# MIL_STD_1275D.net
KiCad netlist of a schematic drawn in Altium Designer
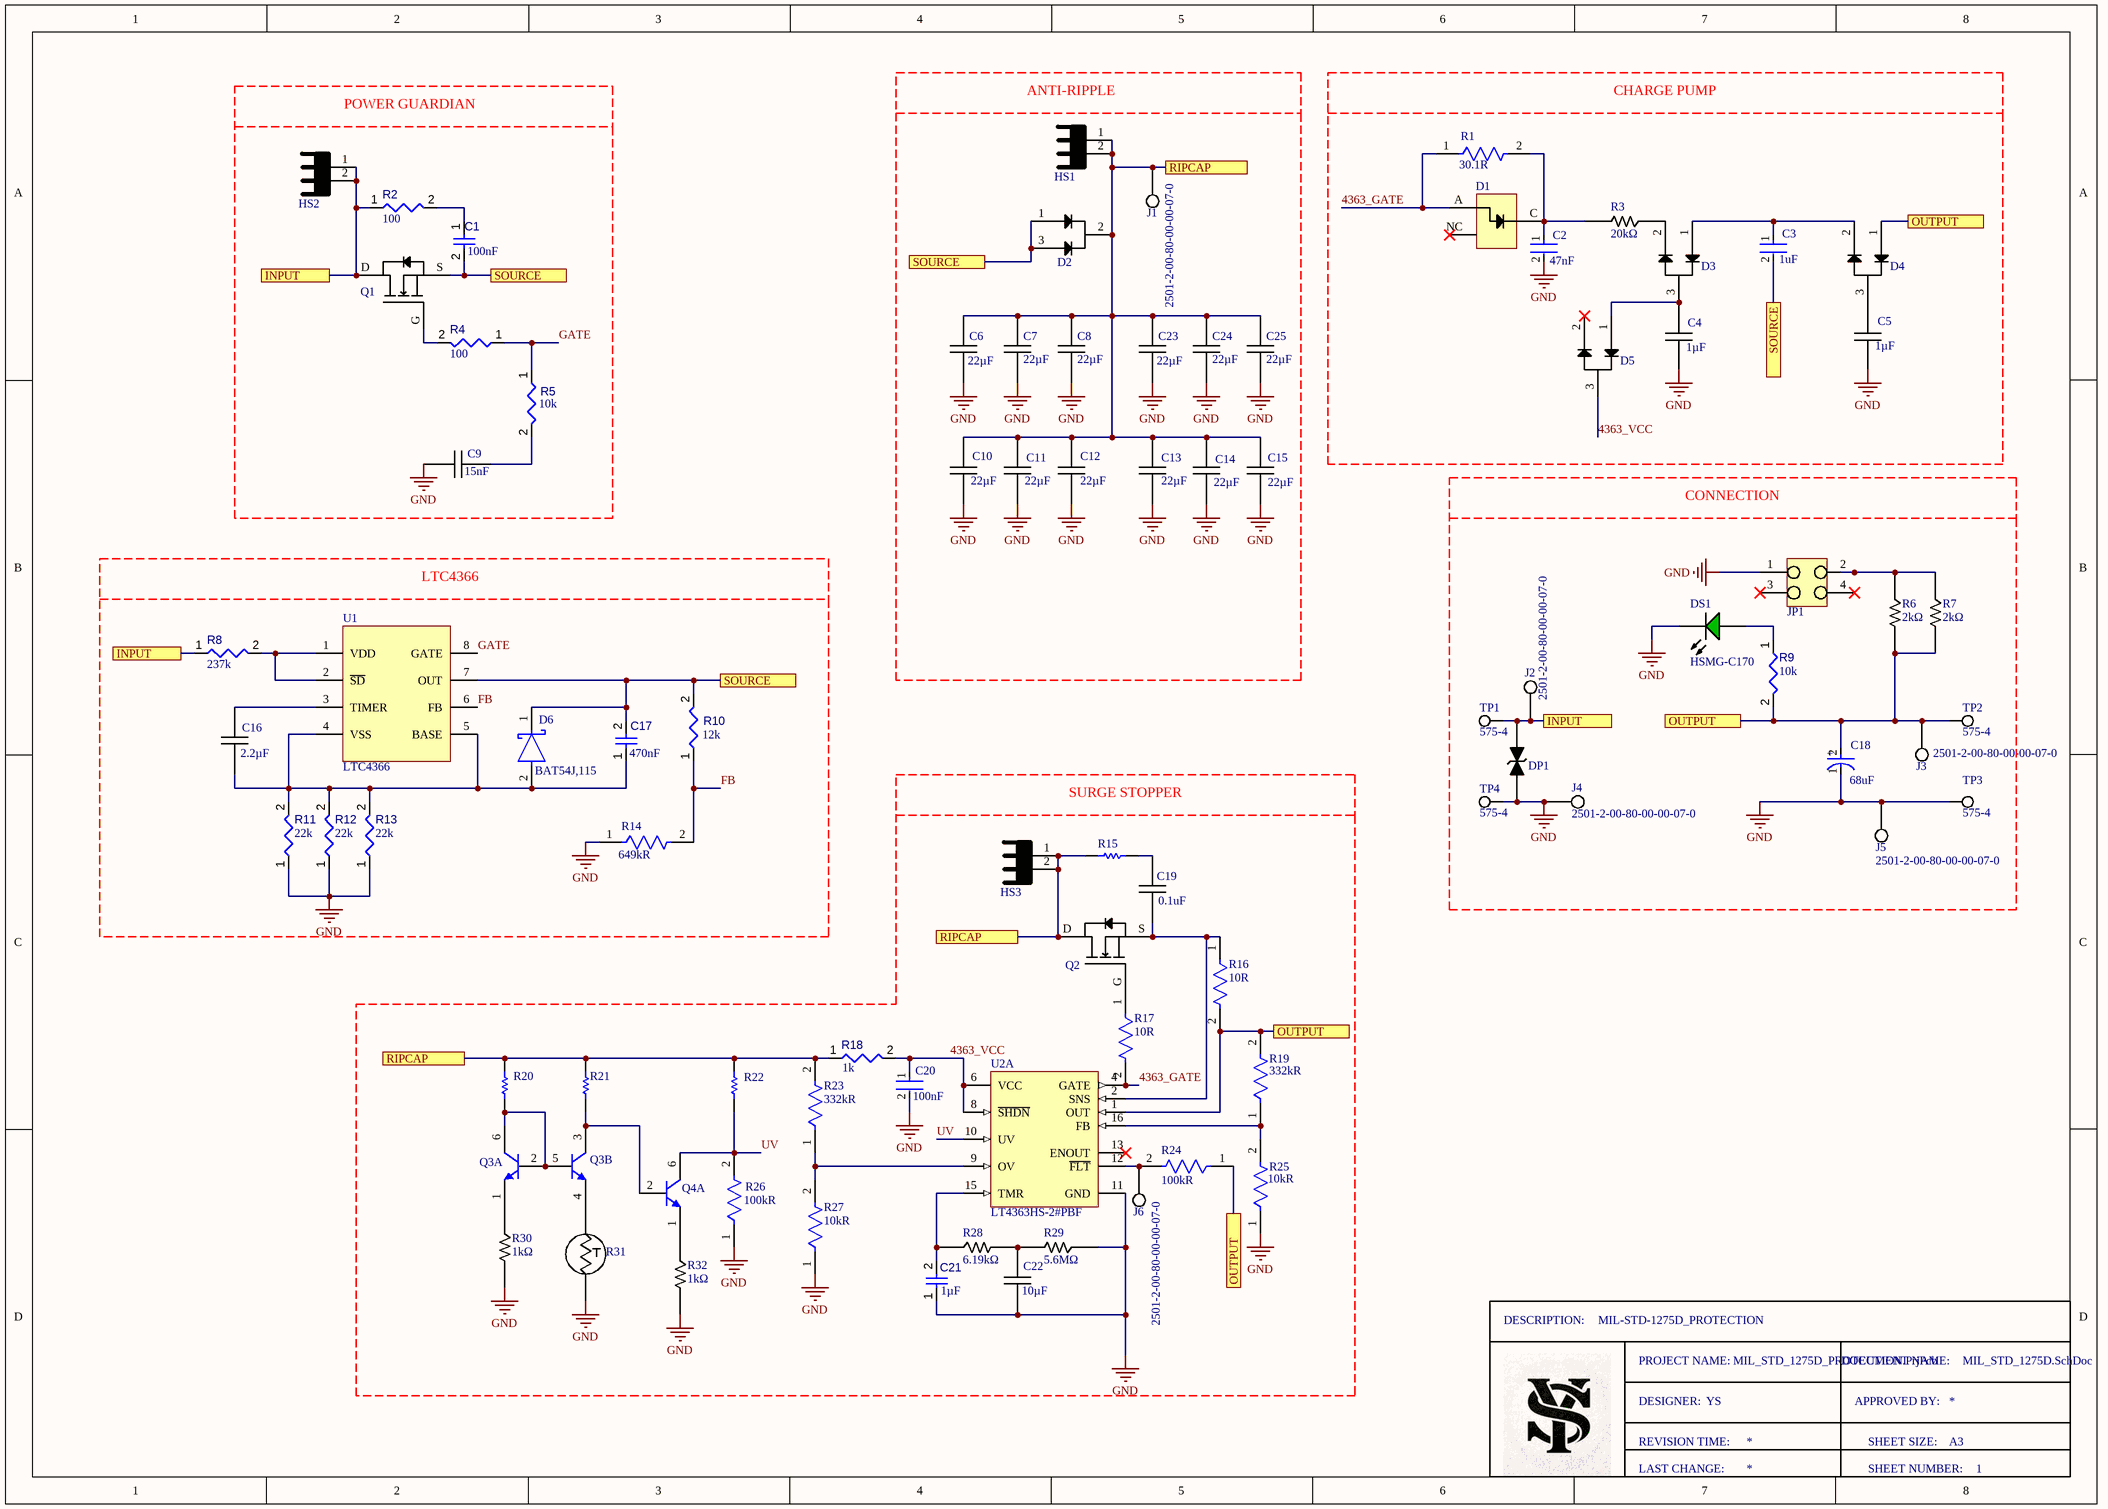
[diagram p0: MIL_STD_1275D.SchDoc]

(export (version "E")
  (design (tool "Eeschema 10.0.6"))
  (components
    (comp (ref "C1")
      (value "100nF")
      (footprint "CAPC0402(1005)60_L")
      (description "Chip Capacitor, 100nF +/-20%, 25V, 0402, Thickness 0.6 mm")
      (fields (field (name "TOLERANCE") "10%") (field (name "Comment") "Capacitor 100nF +/-20% 25V 0402"))
      (libsource (lib "Yigithan Sarı") (part "CAP-NP-2"))
    )
    (comp (ref "C2")
      (value "C2012X7R2A473K125AA")
      (footprint "FP-C2012-125-0_2-IPC_B")
      (description "Multilayer Ceramic Capacitors 47nF ±10% 100V X7R SMD 0805")
      (fields
        (field (name "VOLTAGE") "100V")
        (field (name "CAPACITANCE") "47nF")
        (field (name "TOLERANCE") "10%")
      )
      (libsource (lib "Altium Content Vault") (part "b4654b650e69147ec39a6b967a45e02"))
    )
    (comp (ref "C3")
      (value "C5750X7R2E105K230KA")
      (footprint "FP-C5750-230-0_4-MFG")
      (description "Multilayer Ceramic Capacitors 1uF ±10% 250V X7R SMD 2220")
      (fields
        (field (name "TOLERANCE") "10%")
        (field (name "VOLTAGE") "250V")
        (field (name "CAPACITANCE") "1uF")
      )
      (libsource (lib "Altium Content Vault") (part "02cd4be3c70576c341d710602a673aa"))
    )
    (comp (ref "C4")
      (value "1µF")
      (footprint "CAP_2220")
      (description "250V 1uF X7R 卤10% 2220 Multilayer Ceramic Capacitors MLCC - SMD/SMT ROHS")
      (fields
        (field (name "MANUFACTURER") "TDK")
        (field (name "MANUFACTURER PART NUMBER") "C5750X7R2E105K230KA")
        (field (name "DESIGNED BY") "YS")
      )
      (libsource (lib "DC2150A") (part "C5750X7R2E105K230KA"))
    )
    (comp (ref "C5")
      (value "1µF")
      (footprint "CAP_2220")
      (description "250V 1uF X7R 卤10% 2220 Multilayer Ceramic Capacitors MLCC - SMD/SMT ROHS")
      (fields
        (field (name "MANUFACTURER") "TDK")
        (field (name "MANUFACTURER PART NUMBER") "C5750X7R2E105K230KA")
        (field (name "DESIGNED BY") "YS")
      )
      (libsource (lib "DC2150A") (part "C5750X7R2E105K230KA"))
    )
    (comp (ref "C6")
      (value "22µF")
      (footprint "2 J-LEAD CAP")
      (description "Multilayer Ceramic Capacitor, CKG Series, 22 - F, - 20%, X7S, 100 V, 2220 [5750 Metric]")
      (fields
        (field (name "MANUFACTURER") "TDK")
        (field (name "MANUFACTURER PART NUMBER") "CKG57NX7S2A226M500JH")
        (field (name "DESIGNED BY") "YS")
      )
      (libsource (lib "DC2150A") (part "CKG57NX7S2A226M500JH"))
    )
    (comp (ref "C7")
      (value "22µF")
      (footprint "2 J-LEAD CAP")
      (description "Multilayer Ceramic Capacitor, CKG Series, 22 - F, - 20%, X7S, 100 V, 2220 [5750 Metric]")
      (fields
        (field (name "MANUFACTURER") "TDK")
        (field (name "MANUFACTURER PART NUMBER") "CKG57NX7S2A226M500JH")
        (field (name "DESIGNED BY") "YS")
      )
      (libsource (lib "DC2150A") (part "CKG57NX7S2A226M500JH"))
    )
    (comp (ref "C8")
      (value "22µF")
      (footprint "2 J-LEAD CAP")
      (description "Multilayer Ceramic Capacitor, CKG Series, 22 - F, - 20%, X7S, 100 V, 2220 [5750 Metric]")
      (fields
        (field (name "MANUFACTURER") "TDK")
        (field (name "MANUFACTURER PART NUMBER") "CKG57NX7S2A226M500JH")
        (field (name "DESIGNED BY") "YS")
      )
      (libsource (lib "DC2150A") (part "CKG57NX7S2A226M500JH"))
    )
    (comp (ref "C9")
      (value "15nF")
      (footprint "CAP_1206")
      (description "Cap Ceramic 0.015uF 100V X7R 10% Pad SMD 1206 125C T/R")
      (fields
        (field (name "MANUFACTURER") "Yageo Group")
        (field (name "MANUFACTURER PART NUMBER") "C1206C153K1RACTU")
        (field (name "DESIGNED BY") "YS")
      )
      (libsource (lib "DC2150A") (part "C1206C153K1RACTU (2)"))
    )
    (comp (ref "C10")
      (value "22µF")
      (footprint "2 J-LEAD CAP")
      (description "Multilayer Ceramic Capacitor, CKG Series, 22 - F, - 20%, X7S, 100 V, 2220 [5750 Metric]")
      (fields
        (field (name "MANUFACTURER") "TDK")
        (field (name "MANUFACTURER PART NUMBER") "CKG57NX7S2A226M500JH")
        (field (name "DESIGNED BY") "YS")
      )
      (libsource (lib "DC2150A") (part "CKG57NX7S2A226M500JH"))
    )
    (comp (ref "C11")
      (value "22µF")
      (footprint "2 J-LEAD CAP")
      (description "Multilayer Ceramic Capacitor, CKG Series, 22 - F, - 20%, X7S, 100 V, 2220 [5750 Metric]")
      (fields
        (field (name "MANUFACTURER") "TDK")
        (field (name "MANUFACTURER PART NUMBER") "CKG57NX7S2A226M500JH")
        (field (name "DESIGNED BY") "YS")
      )
      (libsource (lib "DC2150A") (part "CKG57NX7S2A226M500JH"))
    )
    (comp (ref "C12")
      (value "22µF")
      (footprint "2 J-LEAD CAP")
      (description "Multilayer Ceramic Capacitor, CKG Series, 22 - F, - 20%, X7S, 100 V, 2220 [5750 Metric]")
      (fields
        (field (name "MANUFACTURER") "TDK")
        (field (name "MANUFACTURER PART NUMBER") "CKG57NX7S2A226M500JH")
        (field (name "DESIGNED BY") "YS")
      )
      (libsource (lib "DC2150A") (part "CKG57NX7S2A226M500JH"))
    )
    (comp (ref "C13")
      (value "22µF")
      (footprint "2 J-LEAD CAP")
      (description "Multilayer Ceramic Capacitor, CKG Series, 22 - F, - 20%, X7S, 100 V, 2220 [5750 Metric]")
      (fields
        (field (name "MANUFACTURER") "TDK")
        (field (name "MANUFACTURER PART NUMBER") "CKG57NX7S2A226M500JH")
        (field (name "DESIGNED BY") "YS")
      )
      (libsource (lib "DC2150A") (part "CKG57NX7S2A226M500JH"))
    )
    (comp (ref "C14")
      (value "22µF")
      (footprint "2 J-LEAD CAP")
      (description "Multilayer Ceramic Capacitor, CKG Series, 22 - F, - 20%, X7S, 100 V, 2220 [5750 Metric]")
      (fields
        (field (name "MANUFACTURER") "TDK")
        (field (name "MANUFACTURER PART NUMBER") "CKG57NX7S2A226M500JH")
        (field (name "DESIGNED BY") "YS")
      )
      (libsource (lib "DC2150A") (part "CKG57NX7S2A226M500JH"))
    )
    (comp (ref "C15")
      (value "22µF")
      (footprint "2 J-LEAD CAP")
      (description "Multilayer Ceramic Capacitor, CKG Series, 22 - F, - 20%, X7S, 100 V, 2220 [5750 Metric]")
      (fields
        (field (name "MANUFACTURER") "TDK")
        (field (name "MANUFACTURER PART NUMBER") "CKG57NX7S2A226M500JH")
        (field (name "DESIGNED BY") "YS")
      )
      (libsource (lib "DC2150A") (part "CKG57NX7S2A226M500JH"))
    )
    (comp (ref "C16")
      (value "2.2µF")
      (footprint "CAP_0805")
      (description "25V 2.2uF X7R ±10% 0805 Multilayer Ceramic Capacitors MLCC - SMD/SMT ROHS")
      (fields
        (field (name "MANUFACTURER") "TDK")
        (field (name "MANUFACTURER PART NUMBER") "CGA4J3X7R1E225K125AB")
        (field (name "DESIGNED BY") "YS")
      )
      (libsource (lib "DC2150A") (part "CGA4J3X7R1E225K125AB"))
    )
    (comp (ref "C17")
      (value "470nF")
      (footprint "CAPC0603(1608)100_L")
      (description "Chip Capacitor, 470nF +/-20%, 25V, 0603, Thickness 1 mm")
      (fields (field (name "TOLERANCE") "10%") (field (name "Comment") "Capacitor 470nF +/-20% 25V 0603"))
      (libsource (lib "Yigithan Sarı") (part "CAP-NP-2"))
    )
    (comp (ref "C18")
      (value "50SVPF68M")
      (footprint "FP-OS-CON-SMT-F12-MFG")
      (description "Conductive Polymer Aluminum Solid Capacitors (OS-CON) 68uF ±20% 50V RADIAL SMT 10x12.6mm")
      (fields
        (field (name "CAPACITANCE") "68uF")
        (field (name "TOLERANCE") "20%")
        (field (name "VOLTAGE") "50V")
      )
      (libsource (lib "Altium Content Vault") (part "a7907c86e72a156c28511143de7831b"))
    )
    (comp (ref "C19")
      (value "0.1uF")
      (footprint "CAP_1210")
      (description "SMD Comm X7R 1210 (3225Metric) ceramic capacitor 0.126Lx0.098W 3.20mmx2.50mm X7R ±10% 0.1muF")
      (fields (field (name "Comment") "CAP_CER_1210_0.1uF"))
      (libsource (lib "DC2150A") (part "C1210C104K1RAC7025 Yageo Group"))
    )
    (comp (ref "C20")
      (value "C2012X7R2A104K125AA")
      (footprint "FP-C2012-125-0_2-IPC_B")
      (description "Multilayer Ceramic Capacitors 100nF ±10% 100V X7R SMD 0805")
      (fields
        (field (name "VOLTAGE") "100V")
        (field (name "CAPACITANCE") "100nF")
        (field (name "TOLERANCE") "10%")
      )
      (libsource (lib "Altium Content Vault") (part "b4654b650e69147ec39a6b967a45e02"))
    )
    (comp (ref "C21")
      (value "1µF")
      (footprint "CAPC1608X90X35ML15T15")
      (description "Chip Capacitor, 1 uF, +/- 10%, 16 V, 0603 (1608 Metric)")
      (fields (field (name "TOLERANCE") "10%") (field (name "Comment") "Capacitor 1uF +/- 10% 16V 0603"))
      (libsource (lib "Yigithan Sarı") (part "CAP-NP-2"))
    )
    (comp (ref "C22")
      (value "10µF")
      (footprint "CAP_0805")
      (description "16V 10uF X7R 卤10% 0805 Multilayer Ceramic Capacitors MLCC - SMD/SMT ROHS")
      (fields
        (field (name "MANUFACTURER") "Samsung Electro-Mechanics")
        (field (name "MANUFACTURER PART NUMBER") "CL21B106KOQNNNE")
        (field (name "DESIGNED BY") "YS")
      )
      (libsource (lib "DC2150A") (part "CL21B106KOQNNNE"))
    )
    (comp (ref "C23")
      (value "22µF")
      (footprint "2 J-LEAD CAP")
      (description "Multilayer Ceramic Capacitor, CKG Series, 22 - F, - 20%, X7S, 100 V, 2220 [5750 Metric]")
      (fields
        (field (name "MANUFACTURER") "TDK")
        (field (name "MANUFACTURER PART NUMBER") "CKG57NX7S2A226M500JH")
        (field (name "DESIGNED BY") "YS")
      )
      (libsource (lib "DC2150A") (part "CKG57NX7S2A226M500JH"))
    )
    (comp (ref "C24")
      (value "22µF")
      (footprint "2 J-LEAD CAP")
      (description "Multilayer Ceramic Capacitor, CKG Series, 22 - F, - 20%, X7S, 100 V, 2220 [5750 Metric]")
      (fields
        (field (name "MANUFACTURER") "TDK")
        (field (name "MANUFACTURER PART NUMBER") "CKG57NX7S2A226M500JH")
        (field (name "DESIGNED BY") "YS")
      )
      (libsource (lib "DC2150A") (part "CKG57NX7S2A226M500JH"))
    )
    (comp (ref "C25")
      (value "22µF")
      (footprint "2 J-LEAD CAP")
      (description "Multilayer Ceramic Capacitor, CKG Series, 22 - F, - 20%, X7S, 100 V, 2220 [5750 Metric]")
      (fields
        (field (name "MANUFACTURER") "TDK")
        (field (name "MANUFACTURER PART NUMBER") "CKG57NX7S2A226M500JH")
        (field (name "DESIGNED BY") "YS")
      )
      (libsource (lib "DC2150A") (part "CKG57NX7S2A226M500JH"))
    )
    (comp (ref "D1")
      (value "DIODE_SMD_250V")
      (footprint "SOT_323")
      (description "Rectifier Diode, 1 Phase, 1 Element, 0.2A, 250V V(RRM), Silicon")
      (fields
        (field (name "MANUFACTURER") "Diodes Inc.")
        (field (name "MANUFACTURER PART NUMBER") "BAS21W-7-F")
      )
      (libsource (lib "DC2150A") (part "BAS21W-7-F"))
    )
    (comp (ref "D2")
      (value "Rectifier Diode, 1 Phase, 2 Element")
      (footprint "TO-247AD")
      (description "Rectifier Diode, 1 Phase, 2 Element, 15A, 400V V(RRM), Silicon, TO-247AD")
      (fields
        (field (name "MANUFACTURER") "Vishay")
        (field (name "MANUFACTURER PART NUMBER") "FEP30GP-E3/45")
        (field (name "DESIGNED BY") "YS")
      )
      (libsource (lib "DC2150A") (part "FEP30GP-E3/45"))
    )
    (comp (ref "D3")
      (value "Rectifier Diode Small Signal Switching")
      (footprint "SOT-23")
      (description "Rectifier Diode Small Signal Switching 350V 0.225A 50ns 3-Pin SOT-23 T/R")
      (fields
        (field (name "MANUFACTURER") "Diodes Inc.")
        (field (name "MANUFACTURER PART NUMBER") "MMBD3004S-7-F")
        (field (name "DESIGNED BY") "YS")
      )
      (libsource (lib "DC2150A") (part "MMBD3004S-7-F"))
    )
    (comp (ref "D4")
      (value "Rectifier Diode Small Signal Switching")
      (footprint "SOT-23")
      (description "Rectifier Diode Small Signal Switching 350V 0.225A 50ns 3-Pin SOT-23 T/R")
      (fields
        (field (name "MANUFACTURER") "Diodes Inc.")
        (field (name "MANUFACTURER PART NUMBER") "MMBD3004S-7-F")
        (field (name "DESIGNED BY") "YS")
      )
      (libsource (lib "DC2150A") (part "MMBD3004S-7-F"))
    )
    (comp (ref "D5")
      (value "Rectifier Diode Small Signal Switching")
      (footprint "SOT-23")
      (description "Rectifier Diode Small Signal Switching 350V 0.225A 50ns 3-Pin SOT-23 T/R")
      (fields
        (field (name "MANUFACTURER") "Diodes Inc.")
        (field (name "MANUFACTURER PART NUMBER") "MMBD3004S-7-F")
        (field (name "DESIGNED BY") "YS")
      )
      (libsource (lib "DC2150A") (part "MMBD3004S-7-F"))
    )
    (comp (ref "D6")
      (value "BAT54J,115")
      (footprint "FP-SOD323F-MFG")
      (description "DIODE SCHOTTKY 30V 200MA SOD323F")
      (libsource (lib "Altium Content Vault") (part "1d6ec82d83fb6aee721767c19dac4b9"))
    )
    (comp (ref "DP1")
      (value "TVS")
      (footprint "DO-214AA")
      (description "Trans Voltage Suppressor Diode, 600W, 128V V(RWM), Bidirectional, 1 Element, Silicon, DO-214AA")
      (fields
        (field (name "MANUFACTURER") "Vishay")
        (field (name "MANUFACTURER PART NUMBER") "P6SMB150CA-E3/52")
      )
      (libsource (lib "DC2150A") (part "P6SMB150CA-E3/52"))
    )
    (comp (ref "DS1")
      (value "HSMG-C170")
      (footprint "AVAG-HSMX-C170_V")
      (description "Chip LED, Green, 2.2 V, -40 to 85 degC, 2-Pin SMD, Pb-Free, Tape and Reel")
      (fields (field (name "MANUFACTURER") "Avago"))
      (libsource (lib "Altium Content Vault") (part "LED_GREEN_A1K2-2"))
    )
    (comp (ref "HS1")
      (value "HEAT_SINK")
      (footprint "HS_VERTICAL")
      (description "Heat Sink SOT-32, TO-220, TOP-3 Aluminum Board Level, Vertical")
      (fields
        (field (name "MANUFACTURER") "ASSMANN WSW Components")
        (field (name "MANUFACTURER PART NUMBER") "V8813X")
        (field (name "DESIGNED BY") "YS")
      )
      (libsource (lib "DC2150A") (part "V8813X"))
    )
    (comp (ref "HS2")
      (value "HEAT_SINK")
      (footprint "HS_VERTICAL")
      (description "Heat Sink SOT-32, TO-220, TOP-3 Aluminum Board Level, Vertical")
      (fields
        (field (name "MANUFACTURER") "ASSMANN WSW Components")
        (field (name "MANUFACTURER PART NUMBER") "V8813X")
        (field (name "DESIGNED BY") "YS")
      )
      (libsource (lib "DC2150A") (part "V8813X"))
    )
    (comp (ref "HS3")
      (value "HEAT_SINK")
      (footprint "HS_VERTICAL")
      (description "Heat Sink SOT-32, TO-220, TOP-3 Aluminum Board Level, Vertical")
      (fields
        (field (name "MANUFACTURER") "ASSMANN WSW Components")
        (field (name "MANUFACTURER PART NUMBER") "V8813X")
        (field (name "DESIGNED BY") "YS")
      )
      (libsource (lib "DC2150A") (part "V8813X"))
    )
    (comp (ref "J1")
      (value "2501-2-00-80-00-00-07-0")
      (footprint "MILMAX_2501-2-00-80-00-00-07-0")
      (description "Terminal Turret Connector Single End 0.219 (5.56mm) Tin")
      (fields (field (name "MF") "Mill-Max Manufacturing"))
      (libsource (lib "2501-2-00-80-00-00-07-0") (part "2501-2-00-80-00-00-07-0"))
    )
    (comp (ref "J2")
      (value "2501-2-00-80-00-00-07-0")
      (footprint "MILMAX_2501-2-00-80-00-00-07-0")
      (description "Terminal Turret Connector Single End 0.219 (5.56mm) Tin")
      (fields (field (name "MF") "Mill-Max Manufacturing"))
      (libsource (lib "2501-2-00-80-00-00-07-0") (part "2501-2-00-80-00-00-07-0"))
    )
    (comp (ref "J3")
      (value "2501-2-00-80-00-00-07-0")
      (footprint "MILMAX_2501-2-00-80-00-00-07-0")
      (description "Terminal Turret Connector Single End 0.219 (5.56mm) Tin")
      (fields (field (name "MF") "Mill-Max Manufacturing"))
      (libsource (lib "2501-2-00-80-00-00-07-0") (part "2501-2-00-80-00-00-07-0"))
    )
    (comp (ref "J4")
      (value "2501-2-00-80-00-00-07-0")
      (footprint "MILMAX_2501-2-00-80-00-00-07-0")
      (description "Terminal Turret Connector Single End 0.219 (5.56mm) Tin")
      (fields (field (name "MF") "Mill-Max Manufacturing"))
      (libsource (lib "2501-2-00-80-00-00-07-0") (part "2501-2-00-80-00-00-07-0"))
    )
    (comp (ref "J5")
      (value "2501-2-00-80-00-00-07-0")
      (footprint "MILMAX_2501-2-00-80-00-00-07-0")
      (description "Terminal Turret Connector Single End 0.219 (5.56mm) Tin")
      (fields (field (name "MF") "Mill-Max Manufacturing"))
      (libsource (lib "2501-2-00-80-00-00-07-0") (part "2501-2-00-80-00-00-07-0"))
    )
    (comp (ref "J6")
      (value "2501-2-00-80-00-00-07-0")
      (footprint "MILMAX_2501-2-00-80-00-00-07-0")
      (description "Terminal Turret Connector Single End 0.219 (5.56mm) Tin")
      (fields (field (name "MF") "Mill-Max Manufacturing"))
      (libsource (lib "2501-2-00-80-00-00-07-0") (part "2501-2-00-80-00-00-07-0"))
    )
    (comp (ref "JP1")
      (value "CONNECTOR")
      (footprint "CONNECTOR_NRPN022PAEN-RC")
      (description "Board Connector, 4 Contact(s), 2 Row(s), Male, Straight, 0.079 inch Pitch, Solder Terminal")
      (fields
        (field (name "MANUFACTURER") "Sullins")
        (field (name "MANUFACTURER PART NUMBER") "NRPN022PAEN-RC")
      )
      (libsource (lib "DC2150A") (part "NRPN022PAEN-RC"))
    )
    (comp (ref "Q1")
      (value "N-CH MOSFET")
      (footprint "TO-3P")
      (description "PolarHT Series 300 V 88 A 40 mOhm Single N-Channel MOSFET - TO-3P")
      (fields
        (field (name "MANUFACTURER") "Littelfuse")
        (field (name "MANUFACTURER PART NUMBER") "IXTQ88N30P")
        (field (name "DESIGNED BY") "YS")
      )
      (libsource (lib "DC2150A") (part "IXTQ88N30P"))
    )
    (comp (ref "Q2")
      (value "N-CH MOSFET")
      (footprint "TO-3P")
      (description "Trans MOSFET N-CH 100V 170A 3-Pin(3+Tab) TO-3P")
      (fields
        (field (name "MANUFACTURER") "Littelfuse")
        (field (name "MANUFACTURER PART NUMBER") "IXTQ170N10P")
        (field (name "DESIGNED BY") "YS")
      )
      (libsource (lib "DC2150A") (part "IXTQ170N10P"))
    )
    (comp (ref "Q3")
      (value "MMDT5551-7-F")
      (footprint "DIOD-SOT-363-6_L")
      (fields (field (name "MANUFACTURER") "DiodesIncorporated"))
      (libsource (lib "Altium Content Vault") (part "BJT-NPN-EBC-EBC-6_A"))
    )
    (comp (ref "Q4")
      (value "MMDT5551-7-F")
      (footprint "DIOD-SOT-363-6_L")
      (fields (field (name "MANUFACTURER") "DiodesIncorporated"))
      (libsource (lib "Altium Content Vault") (part "BJT-NPN-EBC-EBC-6_A"))
    )
    (comp (ref "R1")
      (value "CRCW080530R1FKEA")
      (footprint "FP-CRCW0805-e3-IPC_B")
      (description "RES Thick Film, 30.1Ω, 1%, 0.125W, 100ppm/°C, 0805")
      (fields (field (name "TOLERANCE") "1%") (field (name "RESISTANCE") "30.1R"))
      (libsource (lib "Altium Content Vault") (part "1029c3af85768c4190bb7ad29bc67b5"))
    )
    (comp (ref "R2")
      (value "100")
      (footprint "RESC0402(1005)_L")
      (description "Chip Resistor, 100 Ohms, +/-1 %, 63 mW, -55 to 155 degC, 0402")
      (fields (field (name "POWER") "63mW") (field (name "TOLERANCE") "1%"))
      (libsource (lib "Yigithan Sarı") (part "RES-2"))
    )
    (comp (ref "R3")
      (value "20kΩ")
      (footprint "RES_0805")
      (description "Fixed Resistor, Metal Glaze/Thick Film, 0.125W, 20000ohm, 150V, 5% +/-Tol, Surface Mount, 0805")
      (fields
        (field (name "MANUFACTURER") "Vishay")
        (field (name "MANUFACTURER PART NUMBER") "CRCW080520K0JNEA")
        (field (name "DESIGNED BY") "YS")
      )
      (libsource (lib "DC2150A") (part "CRCW080520K0JNEA"))
    )
    (comp (ref "R4")
      (value "100")
      (footprint "RESC0402(1005)_L")
      (description "Chip Resistor, 100 Ohms, +/-1 %, 63 mW, -55 to 155 degC, 0402")
      (fields (field (name "POWER") "63mW") (field (name "TOLERANCE") "1%"))
      (libsource (lib "Yigithan Sarı") (part "RES-2"))
    )
    (comp (ref "R5")
      (value "10k")
      (footprint "RESC1005X40X25ML05T05")
      (description "Chip Resistor, 10 KOhm, +/- 1%, 63 mW, -55 to 155 degC, 0402 (1005 Metric)")
      (fields (field (name "POWER") "63mW") (field (name "TOLERANCE") "1%"))
      (libsource (lib "Yigithan Sarı") (part "RES-2"))
    )
    (comp (ref "R6")
      (value "2kΩ")
      (footprint "RES_2010")
      (description "Res Thick Film 2010 2K Ohm 1% 1W ±100ppm/C Pad SMD T/R Automotive AEC-Q200")
      (fields
        (field (name "MANUFACTURER") "Vishay")
        (field (name "MANUFACTURER PART NUMBER") "CRCW20102K00FKEFHP")
      )
      (libsource (lib "DC2150A") (part "CRCW20102K00FKEFHP"))
    )
    (comp (ref "R7")
      (value "2kΩ")
      (footprint "RES_2010")
      (description "Res Thick Film 2010 2K Ohm 1% 1W ±100ppm/C Pad SMD T/R Automotive AEC-Q200")
      (fields
        (field (name "MANUFACTURER") "Vishay")
        (field (name "MANUFACTURER PART NUMBER") "CRCW20102K00FKEFHP")
      )
      (libsource (lib "DC2150A") (part "CRCW20102K00FKEFHP"))
    )
    (comp (ref "R8")
      (value "237k")
      (footprint "RESC0402(1005)_L")
      (description "Chip Resistor, 237 kOhms, +/-1 %, 63 mW, -55 to 155 degC, 0402")
      (fields (field (name "POWER") "63mW") (field (name "TOLERANCE") "1%"))
      (libsource (lib "Yigithan Sarı") (part "RES-2"))
    )
    (comp (ref "R9")
      (value "10k")
      (footprint "RESC3216X60X45ML15T20")
      (description "Chip Resistor, 10 KOhm, +/- 1%, 0.25 W, -55 to 155 degC, 1206 (3216 Metric)")
      (fields (field (name "TOLERANCE") "1%") (field (name "POWER") "250mW"))
      (libsource (lib "Yigithan Sarı") (part "RES-2"))
    )
    (comp (ref "R10")
      (value "12k")
      (footprint "RESC0402(1005)_L")
      (description "12K 0.063W 1% 0402 (1005 Metric)  SMD")
      (fields (field (name "TOLERANCE") "1%") (field (name "POWER") "63mW"))
      (libsource (lib "Yigithan Sarı") (part "12KR2F"))
    )
    (comp (ref "R11")
      (value "22k")
      (footprint "RESC0402(1005)_L")
      (description "22K 0.063W 1% 0402 (1005 Metric)  SMD")
      (fields (field (name "TOLERANCE") "1%") (field (name "POWER") "63mW"))
      (libsource (lib "Yigithan Sarı") (part "22KR2F"))
    )
    (comp (ref "R12")
      (value "22k")
      (footprint "RESC0402(1005)_L")
      (description "22K 0.063W 1% 0402 (1005 Metric)  SMD")
      (fields (field (name "TOLERANCE") "1%") (field (name "POWER") "63mW"))
      (libsource (lib "Yigithan Sarı") (part "22KR2F"))
    )
    (comp (ref "R13")
      (value "22k")
      (footprint "RESC0402(1005)_L")
      (description "22K 0.063W 1% 0402 (1005 Metric)  SMD")
      (fields (field (name "TOLERANCE") "1%") (field (name "POWER") "63mW"))
      (libsource (lib "Yigithan Sarı") (part "22KR2F"))
    )
    (comp (ref "R14")
      (value "CRCW1206649KFKEA")
      (footprint "FP-CRCW1206-e3-MFG")
      (description "RES Thick Film, 649kΩ, 1%, 0.25W, 100ppm/°C, 1206")
      (fields (field (name "RESISTANCE") "649kR") (field (name "TOLERANCE") "1%"))
      (libsource (lib "Altium Content Vault") (part "1029c3af85768c4190bb7ad29bc67b5"))
    )
    (comp (ref "R15")
      (value "CRCW1210100RJNEAHP")
      (footprint "RESC3225X60X45NL20T20")
      (fields (field (name "MANUFACTURER") "Vishay Dale"))
      (libsource (lib "Altium Content Vault") (part "RES"))
    )
    (comp (ref "R16")
      (value "CRCW080510R0JNEA")
      (footprint "FP-CRCW0805-e3-IPC_C")
      (description "RES Thick Film, 10Ω, 5%, 0.125W, 200ppm/°C, 0805")
      (fields (field (name "TOLERANCE") "5%") (field (name "RESISTANCE") "10R"))
      (libsource (lib "Altium Content Vault") (part "1029c3af85768c4190bb7ad29bc67b5"))
    )
    (comp (ref "R17")
      (value "CRCW080510R0JNEA")
      (footprint "FP-CRCW0805-e3-IPC_C")
      (description "RES Thick Film, 10Ω, 5%, 0.125W, 200ppm/°C, 0805")
      (fields (field (name "TOLERANCE") "5%") (field (name "RESISTANCE") "10R"))
      (libsource (lib "Altium Content Vault") (part "1029c3af85768c4190bb7ad29bc67b5"))
    )
    (comp (ref "R18")
      (value "1k")
      (footprint "RESC0402(1005)_L")
      (description "1K 0.063W 5% 0402 (1005 Metric)  SMD")
      (fields (field (name "POWER") "63mW") (field (name "TOLERANCE") "5%"))
      (libsource (lib "Yigithan Sarı") (part "1KR2J"))
    )
    (comp (ref "R19")
      (value "CRCW0805332KFKEA")
      (footprint "FP-CRCW0805-e3-IPC_B")
      (description "RES Thick Film, 332kΩ, 1%, 0.125W, 100ppm/°C, 0805")
      (fields (field (name "TOLERANCE") "1%") (field (name "RESISTANCE") "332kR"))
      (libsource (lib "Altium Content Vault") (part "1029c3af85768c4190bb7ad29bc67b5"))
    )
    (comp (ref "R20")
      (value "CRCW0805301KFKEA")
      (footprint "RESC2013X50X30LL20T20")
      (fields (field (name "MANUFACTURER") "Vishay Dale"))
      (libsource (lib "Altium Content Vault") (part "RES"))
    )
    (comp (ref "R21")
      (value "CRCW0805301KFKEA")
      (footprint "RESC2013X50X30LL20T20")
      (fields (field (name "MANUFACTURER") "Vishay Dale"))
      (libsource (lib "Altium Content Vault") (part "RES"))
    )
    (comp (ref "R22")
      (value "CRCW0805301KFKEA")
      (footprint "RESC2013X50X30LL20T20")
      (fields (field (name "MANUFACTURER") "Vishay Dale"))
      (libsource (lib "Altium Content Vault") (part "RES"))
    )
    (comp (ref "R23")
      (value "CRCW0805332KFKEA")
      (footprint "FP-CRCW0805-e3-IPC_B")
      (description "RES Thick Film, 332kΩ, 1%, 0.125W, 100ppm/°C, 0805")
      (fields (field (name "TOLERANCE") "1%") (field (name "RESISTANCE") "332kR"))
      (libsource (lib "Altium Content Vault") (part "1029c3af85768c4190bb7ad29bc67b5"))
    )
    (comp (ref "R24")
      (value "CRCW0805100KFKEA")
      (footprint "FP-CRCW0805-e3-MFG")
      (description "RES Thick Film, 100kΩ, 1%, 0.125W, 100ppm/°C, 0805")
      (fields (field (name "RESISTANCE") "100kR") (field (name "TOLERANCE") "1%"))
      (libsource (lib "Altium Content Vault") (part "1029c3af85768c4190bb7ad29bc67b5"))
    )
    (comp (ref "R25")
      (value "CRCW080510K0FKEA")
      (footprint "FP-CRCW0805-e3-IPC_A")
      (description "RES Thick Film, 10kΩ, 1%, 0.125W, 100ppm/°C, 0805")
      (fields (field (name "RESISTANCE") "10kR") (field (name "TOLERANCE") "1%"))
      (libsource (lib "Altium Content Vault") (part "1029c3af85768c4190bb7ad29bc67b5"))
    )
    (comp (ref "R26")
      (value "CRCW0805100KFKEA")
      (footprint "FP-CRCW0805-e3-MFG")
      (description "RES Thick Film, 100kΩ, 1%, 0.125W, 100ppm/°C, 0805")
      (fields (field (name "RESISTANCE") "100kR") (field (name "TOLERANCE") "1%"))
      (libsource (lib "Altium Content Vault") (part "1029c3af85768c4190bb7ad29bc67b5"))
    )
    (comp (ref "R27")
      (value "CRCW080510K0FKEA")
      (footprint "FP-CRCW0805-e3-IPC_A")
      (description "RES Thick Film, 10kΩ, 1%, 0.125W, 100ppm/°C, 0805")
      (fields (field (name "RESISTANCE") "10kR") (field (name "TOLERANCE") "1%"))
      (libsource (lib "Altium Content Vault") (part "1029c3af85768c4190bb7ad29bc67b5"))
    )
    (comp (ref "R28")
      (value "6.19kΩ")
      (footprint "RES_0805")
      (description "Fixed Resistor, Metal Glaze/Thick Film, 0.125W, 6190ohm, 150V, 1% +/-Tol, Surface Mount, 0805")
      (fields
        (field (name "MANUFACTURER") "Vishay")
        (field (name "MANUFACTURER PART NUMBER") "CRCW08056K19FKEA")
        (field (name "DESIGNED BY") "YS")
      )
      (libsource (lib "DC2150A") (part "CRCW08056K19FKEA"))
    )
    (comp (ref "R29")
      (value "5.6MΩ")
      (footprint "RES_0805")
      (description "Res Thick Film 0805 5.6M Ohm 5% 0.125W(1/8W) -400ppm/C to 150ppm/C Molded SMD Punched T/R")
      (fields
        (field (name "MANUFACTURER") "Panasonic")
        (field (name "MANUFACTURER PART NUMBER") "ERJ-6GEYJ565V")
        (field (name "DESIGNED BY") "YS")
      )
      (libsource (lib "DC2150A") (part "ERJ-6GEYJ565V"))
    )
    (comp (ref "R30")
      (value "1kΩ")
      (footprint "RES_0805")
      (description "125mW Thick Film Resistors 150V ±1% ±100ppm/℃ 1kΩ 0805 Chip Resistor - Surface Mount ROHS")
      (fields
        (field (name "MANUFACTURER") "Vishay")
        (field (name "MANUFACTURER PART NUMBER") "CRCW08051K00FKEA")
        (field (name "DESIGNED BY") "YS")
      )
      (libsource (lib "DC2150A") (part "CRCW08051K00FKEA"))
    )
    (comp (ref "R31")
      (value "THERMISTOR")
      (footprint "THERMISTOR")
      (description "Thermistor PTC 100 Ohm 2-Pin Screw Mount Radial Cardboard Strip")
      (fields (field (name "DESIGNED BY") "YS"))
      (libsource (lib "DC2150A") (part "EPCOS, B59901D100A40"))
    )
    (comp (ref "R32")
      (value "1kΩ")
      (footprint "RES_0805")
      (description "Resistor Thick Film 0805 1K Ohm 5% 0.125W (1/8W) ±200ppm/C Molded Surface Mount Paper")
      (fields
        (field (name "MANUFACTURER") "NIC Components")
        (field (name "MANUFACTURER PART NUMBER") "NRC10J102TRF")
      )
      (libsource (lib "DC2150A") (part "NRC10J102TRF"))
    )
    (comp (ref "TP1")
      (value "575-4")
      (footprint "KSTN-575-4")
      (description "Banana Jack, Non-Insulated, 1-Pin THD, RoHS, Bulk")
      (fields (field (name "MANUFACTURER") "Keystone-Electronics"))
      (libsource (lib "Altium Content Vault") (part "TESTPOINT_WHITE"))
    )
    (comp (ref "TP2")
      (value "575-4")
      (footprint "KSTN-575-4")
      (description "Banana Jack, Non-Insulated, 1-Pin THD, RoHS, Bulk")
      (fields (field (name "MANUFACTURER") "Keystone-Electronics"))
      (libsource (lib "Altium Content Vault") (part "TESTPOINT_WHITE"))
    )
    (comp (ref "TP3")
      (value "575-4")
      (footprint "KSTN-575-4")
      (description "Banana Jack, Non-Insulated, 1-Pin THD, RoHS, Bulk")
      (fields (field (name "MANUFACTURER") "Keystone-Electronics"))
      (libsource (lib "Altium Content Vault") (part "TESTPOINT_WHITE"))
    )
    (comp (ref "TP4")
      (value "575-4")
      (footprint "KSTN-575-4")
      (description "Banana Jack, Non-Insulated, 1-Pin THD, RoHS, Bulk")
      (fields (field (name "MANUFACTURER") "Keystone-Electronics"))
      (libsource (lib "Altium Content Vault") (part "TESTPOINT_WHITE"))
    )
    (comp (ref "U1")
      (value "LTC4366")
      (footprint "TSOT_23")
      (description "Ms-Hot Swap/High Voltage High Voltage Surge Stopper With Auto-Retry")
      (fields
        (field (name "MANUFACTURER") "Analog Devices")
        (field (name "MANUFACTURER PART NUMBER") "LTC4366HTS8-2#TRPBF")
        (field (name "DESIGNED BY") "YS")
      )
      (libsource (lib "DC2150A") (part "LTC4366HTS8-2#TRPBF"))
    )
    (comp (ref "U2")
      (value "LT4363HS-2#PBF")
      (footprint "LT-S-16_N")
      (fields (field (name "MANUFACTURER") "Linear Technology"))
      (libsource (lib "Altium Content Vault") (part "LT-LT4363-2-S-16"))
    )
  )
  (nets
    (net (code "1") (name "/4363_GATE") (class "Default")
      (node (ref "D1") (pin "A") (pinfunction "A_A") (pintype "passive"))
      (node (ref "R1") (pin "1") (pinfunction "1_1") (pintype "passive"))
      (node (ref "R17") (pin "2") (pinfunction "2_2") (pintype "passive"))
      (node (ref "U2") (pin "4") (pinfunction "GATE_4") (pintype "output"))
    )
    (net (code "2") (name "/4363_VCC") (class "Default")
      (node (ref "C20") (pin "1") (pinfunction "1_1") (pintype "passive"))
      (node (ref "D5") (pin "3") (pinfunction "3_3") (pintype "passive"))
      (node (ref "R18") (pin "2") (pinfunction "2_2") (pintype "passive"))
      (node (ref "U2") (pin "6") (pinfunction "VCC_6") (pintype "power_in"))
      (node (ref "U2") (pin "8") (pinfunction "~{SHDN}_8") (pintype "input"))
    )
    (net (code "3") (name "/FB") (class "Default")
      (node (ref "R10") (pin "1") (pinfunction "1_1") (pintype "passive"))
      (node (ref "R14") (pin "2") (pinfunction "2_2") (pintype "passive"))
      (node (ref "U1") (pin "6") (pinfunction "FB_6") (pintype "passive"))
    )
    (net (code "4") (name "/GATE") (class "Default")
      (node (ref "R4") (pin "1") (pinfunction "1_1") (pintype "passive"))
      (node (ref "R5") (pin "1") (pinfunction "1_1") (pintype "passive"))
      (node (ref "U1") (pin "8") (pinfunction "GATE_8") (pintype "passive"))
    )
    (net (code "5") (name "/INPUT") (class "Default")
      (node (ref "DP1") (pin "2") (pinfunction "2_2") (pintype "passive"))
      (node (ref "HS2") (pin "1") (pinfunction "1_1") (pintype "passive"))
      (node (ref "HS2") (pin "2") (pinfunction "2_2") (pintype "passive"))
      (node (ref "J2") (pin "1") (pinfunction "1_1") (pintype "passive"))
      (node (ref "Q1") (pin "D") (pintype "passive"))
      (node (ref "R2") (pin "1") (pinfunction "1_1") (pintype "passive"))
      (node (ref "R8") (pin "1") (pinfunction "1_1") (pintype "passive"))
      (node (ref "TP1") (pin "1") (pinfunction "1_1") (pintype "passive"))
    )
    (net (code "6") (name "/OUTPUT") (class "Default")
      (node (ref "C18") (pin "2") (pinfunction "A_2") (pintype "passive"))
      (node (ref "D4") (pin "1") (pinfunction "1_1") (pintype "passive"))
      (node (ref "J3") (pin "1") (pinfunction "1_1") (pintype "passive"))
      (node (ref "R16") (pin "2") (pinfunction "2_2") (pintype "passive"))
      (node (ref "R19") (pin "2") (pinfunction "2_2") (pintype "passive"))
      (node (ref "R24") (pin "1") (pinfunction "1_1") (pintype "passive"))
      (node (ref "R6") (pin "1") (pintype "passive"))
      (node (ref "R7") (pin "1") (pintype "passive"))
      (node (ref "R9") (pin "2") (pinfunction "2_2") (pintype "passive"))
      (node (ref "TP2") (pin "1") (pinfunction "1_1") (pintype "passive"))
      (node (ref "U2") (pin "1") (pinfunction "OUT_1") (pintype "input"))
    )
    (net (code "7") (name "/RIPCAP") (class "Default")
      (node (ref "C10") (pin "2") (pintype "passive"))
      (node (ref "C11") (pin "2") (pintype "passive"))
      (node (ref "C12") (pin "2") (pintype "passive"))
      (node (ref "C13") (pin "2") (pintype "passive"))
      (node (ref "C14") (pin "2") (pintype "passive"))
      (node (ref "C15") (pin "2") (pintype "passive"))
      (node (ref "C23") (pin "2") (pintype "passive"))
      (node (ref "C24") (pin "2") (pintype "passive"))
      (node (ref "C25") (pin "2") (pintype "passive"))
      (node (ref "C6") (pin "2") (pintype "passive"))
      (node (ref "C7") (pin "2") (pintype "passive"))
      (node (ref "C8") (pin "2") (pintype "passive"))
      (node (ref "D2") (pin "2") (pinfunction "2_2") (pintype "passive"))
      (node (ref "HS1") (pin "1") (pinfunction "1_1") (pintype "passive"))
      (node (ref "HS1") (pin "2") (pinfunction "2_2") (pintype "passive"))
      (node (ref "HS3") (pin "1") (pinfunction "1_1") (pintype "passive"))
      (node (ref "HS3") (pin "2") (pinfunction "2_2") (pintype "passive"))
      (node (ref "J1") (pin "1") (pinfunction "1_1") (pintype "passive"))
      (node (ref "Q2") (pin "D") (pintype "passive"))
      (node (ref "R15") (pin "1") (pinfunction "1_1") (pintype "passive"))
      (node (ref "R18") (pin "1") (pinfunction "1_1") (pintype "passive"))
      (node (ref "R20") (pin "2") (pinfunction "2_2") (pintype "passive"))
      (node (ref "R21") (pin "2") (pinfunction "2_2") (pintype "passive"))
      (node (ref "R22") (pin "2") (pinfunction "2_2") (pintype "passive"))
      (node (ref "R23") (pin "2") (pinfunction "2_2") (pintype "passive"))
    )
    (net (code "8") (name "/SOURCE") (class "Default")
      (node (ref "C1") (pin "2") (pinfunction "2_2") (pintype "passive"))
      (node (ref "C17") (pin "2") (pinfunction "2_2") (pintype "passive"))
      (node (ref "C3") (pin "2") (pinfunction "2_2") (pintype "passive"))
      (node (ref "D2") (pin "1") (pinfunction "1_1") (pintype "passive"))
      (node (ref "D2") (pin "3") (pinfunction "3_3") (pintype "passive"))
      (node (ref "D6") (pin "1") (pinfunction "C_1") (pintype "passive"))
      (node (ref "Q1") (pin "S") (pintype "passive"))
      (node (ref "R10") (pin "2") (pinfunction "2_2") (pintype "passive"))
      (node (ref "U1") (pin "7") (pinfunction "OUT_7") (pintype "passive"))
    )
    (net (code "9") (name "/UV") (class "Default")
      (node (ref "Q4") (pin "6") (pinfunction "C1_6") (pintype "passive"))
      (node (ref "R22") (pin "1") (pinfunction "1_1") (pintype "passive"))
      (node (ref "R26") (pin "2") (pinfunction "2_2") (pintype "passive"))
      (node (ref "U2") (pin "10") (pinfunction "UV_10") (pintype "input"))
    )
    (net (code "10") (name "GND") (class "Default")
      (node (ref "C10") (pin "1") (pintype "passive"))
      (node (ref "C11") (pin "1") (pintype "passive"))
      (node (ref "C12") (pin "1") (pintype "passive"))
      (node (ref "C13") (pin "1") (pintype "passive"))
      (node (ref "C14") (pin "1") (pintype "passive"))
      (node (ref "C15") (pin "1") (pintype "passive"))
      (node (ref "C18") (pin "1") (pinfunction "C_1") (pintype "passive"))
      (node (ref "C2") (pin "2") (pinfunction "2_2") (pintype "passive"))
      (node (ref "C20") (pin "2") (pinfunction "2_2") (pintype "passive"))
      (node (ref "C21") (pin "1") (pinfunction "1_1") (pintype "passive"))
      (node (ref "C22") (pin "1") (pintype "passive"))
      (node (ref "C23") (pin "1") (pintype "passive"))
      (node (ref "C24") (pin "1") (pintype "passive"))
      (node (ref "C25") (pin "1") (pintype "passive"))
      (node (ref "C4") (pin "2") (pintype "passive"))
      (node (ref "C5") (pin "2") (pintype "passive"))
      (node (ref "C6") (pin "1") (pintype "passive"))
      (node (ref "C7") (pin "1") (pintype "passive"))
      (node (ref "C8") (pin "1") (pintype "passive"))
      (node (ref "C9") (pin "1") (pintype "passive"))
      (node (ref "DP1") (pin "1") (pinfunction "1_1") (pintype "passive"))
      (node (ref "DS1") (pin "2") (pinfunction "K_2") (pintype "passive"))
      (node (ref "J4") (pin "1") (pinfunction "1_1") (pintype "passive"))
      (node (ref "J5") (pin "1") (pinfunction "1_1") (pintype "passive"))
      (node (ref "JP1") (pin "1") (pinfunction "1_1") (pintype "passive"))
      (node (ref "R11") (pin "1") (pinfunction "1_1") (pintype "passive"))
      (node (ref "R12") (pin "1") (pinfunction "1_1") (pintype "passive"))
      (node (ref "R13") (pin "1") (pinfunction "1_1") (pintype "passive"))
      (node (ref "R14") (pin "1") (pinfunction "1_1") (pintype "passive"))
      (node (ref "R25") (pin "1") (pinfunction "1_1") (pintype "passive"))
      (node (ref "R26") (pin "1") (pinfunction "1_1") (pintype "passive"))
      (node (ref "R27") (pin "1") (pinfunction "1_1") (pintype "passive"))
      (node (ref "R29") (pin "2") (pinfunction "2_2") (pintype "passive"))
      (node (ref "R30") (pin "1") (pintype "passive"))
      (node (ref "R31") (pin "1") (pinfunction "1_1") (pintype "passive"))
      (node (ref "R32") (pin "1") (pintype "passive"))
      (node (ref "TP3") (pin "1") (pinfunction "1_1") (pintype "passive"))
      (node (ref "TP4") (pin "1") (pinfunction "1_1") (pintype "passive"))
      (node (ref "U2") (pin "11") (pinfunction "GND_11") (pintype "power_in"))
    )
    (net (code "11") (name "Net-(C1-Pad1)") (class "Default")
      (node (ref "C1") (pin "1") (pinfunction "1_1") (pintype "passive"))
      (node (ref "R2") (pin "2") (pinfunction "2_2") (pintype "passive"))
    )
    (net (code "12") (name "Net-(C2-Pad1)") (class "Default")
      (node (ref "C2") (pin "1") (pinfunction "1_1") (pintype "passive"))
      (node (ref "D1") (pin "C") (pinfunction "C_C") (pintype "passive"))
      (node (ref "R1") (pin "2") (pinfunction "2_2") (pintype "passive"))
      (node (ref "R3") (pin "1") (pintype "passive"))
    )
    (net (code "13") (name "Net-(C3-Pad1)") (class "Default")
      (node (ref "C3") (pin "1") (pinfunction "1_1") (pintype "passive"))
      (node (ref "D3") (pin "1") (pinfunction "1_1") (pintype "passive"))
      (node (ref "D4") (pin "2") (pinfunction "2_2") (pintype "passive"))
    )
    (net (code "14") (name "Net-(C4-Pad1)") (class "Default")
      (node (ref "C4") (pin "1") (pintype "passive"))
      (node (ref "D3") (pin "3") (pinfunction "3_3") (pintype "passive"))
      (node (ref "D5") (pin "1") (pinfunction "1_1") (pintype "passive"))
    )
    (net (code "15") (name "Net-(C5-Pad1)") (class "Default")
      (node (ref "C5") (pin "1") (pintype "passive"))
      (node (ref "D4") (pin "3") (pinfunction "3_3") (pintype "passive"))
    )
    (net (code "16") (name "Net-(C9-Pad2)") (class "Default")
      (node (ref "C9") (pin "2") (pintype "passive"))
      (node (ref "R5") (pin "2") (pinfunction "2_2") (pintype "passive"))
    )
    (net (code "17") (name "Net-(C19-Pad2)") (class "Default")
      (node (ref "C19") (pin "2") (pintype "passive"))
      (node (ref "R15") (pin "2") (pinfunction "2_2") (pintype "passive"))
    )
    (net (code "18") (name "Net-(C22-Pad2)") (class "Default")
      (node (ref "C22") (pin "2") (pintype "passive"))
      (node (ref "R28") (pin "1") (pintype "passive"))
      (node (ref "R29") (pin "1") (pintype "passive"))
    )
    (net (code "19") (name "Net-(D3-Pad2)") (class "Default")
      (node (ref "D3") (pin "2") (pinfunction "2_2") (pintype "passive"))
      (node (ref "R3") (pin "2") (pinfunction "2_2") (pintype "passive"))
    )
    (net (code "20") (name "Net-(D6-A)") (class "Default")
      (node (ref "C16") (pin "1") (pintype "passive"))
      (node (ref "C17") (pin "1") (pinfunction "1_1") (pintype "passive"))
      (node (ref "D6") (pin "2") (pinfunction "A_2") (pintype "passive"))
      (node (ref "R11") (pin "2") (pinfunction "2_2") (pintype "passive"))
      (node (ref "R12") (pin "2") (pinfunction "2_2") (pintype "passive"))
      (node (ref "R13") (pin "2") (pinfunction "2_2") (pintype "passive"))
      (node (ref "U1") (pin "4") (pinfunction "VSS_4") (pintype "passive"))
      (node (ref "U1") (pin "5") (pinfunction "BASE_5") (pintype "passive"))
    )
    (net (code "21") (name "Net-(DS1-A)") (class "Default")
      (node (ref "DS1") (pin "1") (pinfunction "A_1") (pintype "passive"))
      (node (ref "R9") (pin "1") (pinfunction "1_1") (pintype "passive"))
    )
    (net (code "22") (name "Net-(JP1-Pad2)") (class "Default")
      (node (ref "JP1") (pin "2") (pinfunction "2_2") (pintype "passive"))
      (node (ref "R6") (pin "2") (pinfunction "2_2") (pintype "passive"))
      (node (ref "R7") (pin "2") (pinfunction "2_2") (pintype "passive"))
    )
    (net (code "23") (name "Net-(Q1-PadG)") (class "Default")
      (node (ref "Q1") (pin "G") (pintype "passive"))
      (node (ref "R4") (pin "2") (pinfunction "2_2") (pintype "passive"))
    )
    (net (code "24") (name "Net-(Q2-PadG)") (class "Default")
      (node (ref "Q2") (pin "G") (pintype "passive"))
      (node (ref "R17") (pin "1") (pinfunction "1_1") (pintype "passive"))
    )
    (net (code "25") (name "Net-(Q3A-B1)") (class "Default")
      (node (ref "Q3") (pin "2") (pinfunction "B1_2") (pintype "passive"))
      (node (ref "Q3") (pin "5") (pinfunction "B2_5") (pintype "passive"))
      (node (ref "Q3") (pin "6") (pinfunction "C1_6") (pintype "passive"))
      (node (ref "R20") (pin "1") (pinfunction "1_1") (pintype "passive"))
    )
    (net (code "26") (name "Net-(Q3A-E1)") (class "Default")
      (node (ref "Q3") (pin "1") (pinfunction "E1_1") (pintype "passive"))
      (node (ref "R30") (pin "2") (pinfunction "2_2") (pintype "passive"))
    )
    (net (code "27") (name "Net-(Q3B-C2)") (class "Default")
      (node (ref "Q3") (pin "3") (pinfunction "C2_3") (pintype "passive"))
      (node (ref "Q4") (pin "2") (pinfunction "B1_2") (pintype "passive"))
      (node (ref "R21") (pin "1") (pinfunction "1_1") (pintype "passive"))
    )
    (net (code "28") (name "Net-(Q3B-E2)") (class "Default")
      (node (ref "Q3") (pin "4") (pinfunction "E2_4") (pintype "passive"))
      (node (ref "R31") (pin "2") (pinfunction "2_2") (pintype "passive"))
    )
    (net (code "29") (name "Net-(Q4A-E1)") (class "Default")
      (node (ref "Q4") (pin "1") (pinfunction "E1_1") (pintype "passive"))
      (node (ref "R32") (pin "2") (pinfunction "2_2") (pintype "passive"))
    )
    (net (code "30") (name "Net-(U1-TIMER)") (class "Default")
      (node (ref "C16") (pin "2") (pintype "passive"))
      (node (ref "U1") (pin "3") (pinfunction "TIMER_3") (pintype "passive"))
    )
    (net (code "31") (name "Net-(U1-VDD)") (class "Default")
      (node (ref "R8") (pin "2") (pinfunction "2_2") (pintype "passive"))
      (node (ref "U1") (pin "1") (pinfunction "VDD_1") (pintype "passive"))
      (node (ref "U1") (pin "2") (pinfunction "~{SD}_2") (pintype "passive"))
    )
    (net (code "32") (name "Net-(U2A-FB)") (class "Default")
      (node (ref "R19") (pin "1") (pinfunction "1_1") (pintype "passive"))
      (node (ref "R25") (pin "2") (pinfunction "2_2") (pintype "passive"))
      (node (ref "U2") (pin "16") (pinfunction "FB_16") (pintype "input"))
    )
    (net (code "33") (name "Net-(U2A-OV)") (class "Default")
      (node (ref "R23") (pin "1") (pinfunction "1_1") (pintype "passive"))
      (node (ref "R27") (pin "2") (pinfunction "2_2") (pintype "passive"))
      (node (ref "U2") (pin "9") (pinfunction "OV_9") (pintype "input"))
    )
    (net (code "34") (name "Net-(U2A-SNS)") (class "Default")
      (node (ref "C19") (pin "1") (pintype "passive"))
      (node (ref "Q2") (pin "S") (pintype "passive"))
      (node (ref "R16") (pin "1") (pinfunction "1_1") (pintype "passive"))
      (node (ref "U2") (pin "2") (pinfunction "SNS_2") (pintype "input"))
    )
    (net (code "35") (name "Net-(U2A-TMR)") (class "Default")
      (node (ref "C21") (pin "2") (pinfunction "2_2") (pintype "passive"))
      (node (ref "R28") (pin "2") (pinfunction "2_2") (pintype "passive"))
      (node (ref "U2") (pin "15") (pinfunction "TMR_15") (pintype "input"))
    )
    (net (code "36") (name "Net-(U2A-~{FLT})") (class "Default")
      (node (ref "J6") (pin "1") (pinfunction "1_1") (pintype "passive"))
      (node (ref "R24") (pin "2") (pinfunction "2_2") (pintype "passive"))
      (node (ref "U2") (pin "12") (pinfunction "~{FLT}_12") (pintype "tri_state"))
    )
    (net (code "37") (name "unconnected-(D1-PadNC)") (class "Default")
      (node (ref "D1") (pin "NC") (pinfunction "NC_NC") (pintype "passive+no_connect"))
    )
    (net (code "38") (name "unconnected-(D5-Pad2)") (class "Default")
      (node (ref "D5") (pin "2") (pinfunction "2_2") (pintype "passive+no_connect"))
    )
    (net (code "39") (name "unconnected-(JP1-Pad3)") (class "Default")
      (node (ref "JP1") (pin "3") (pinfunction "3_3") (pintype "passive+no_connect"))
    )
    (net (code "40") (name "unconnected-(JP1-Pad4)") (class "Default")
      (node (ref "JP1") (pin "4") (pinfunction "4_4") (pintype "passive+no_connect"))
    )
    (net (code "41") (name "unconnected-(U2A-ENOUT-Pad13)") (class "Default")
      (node (ref "U2") (pin "13") (pinfunction "ENOUT_13") (pintype "tri_state+no_connect"))
    )
  )
)
